# Radio.net
KiCad netlist of a schematic drawn in Altium Designer
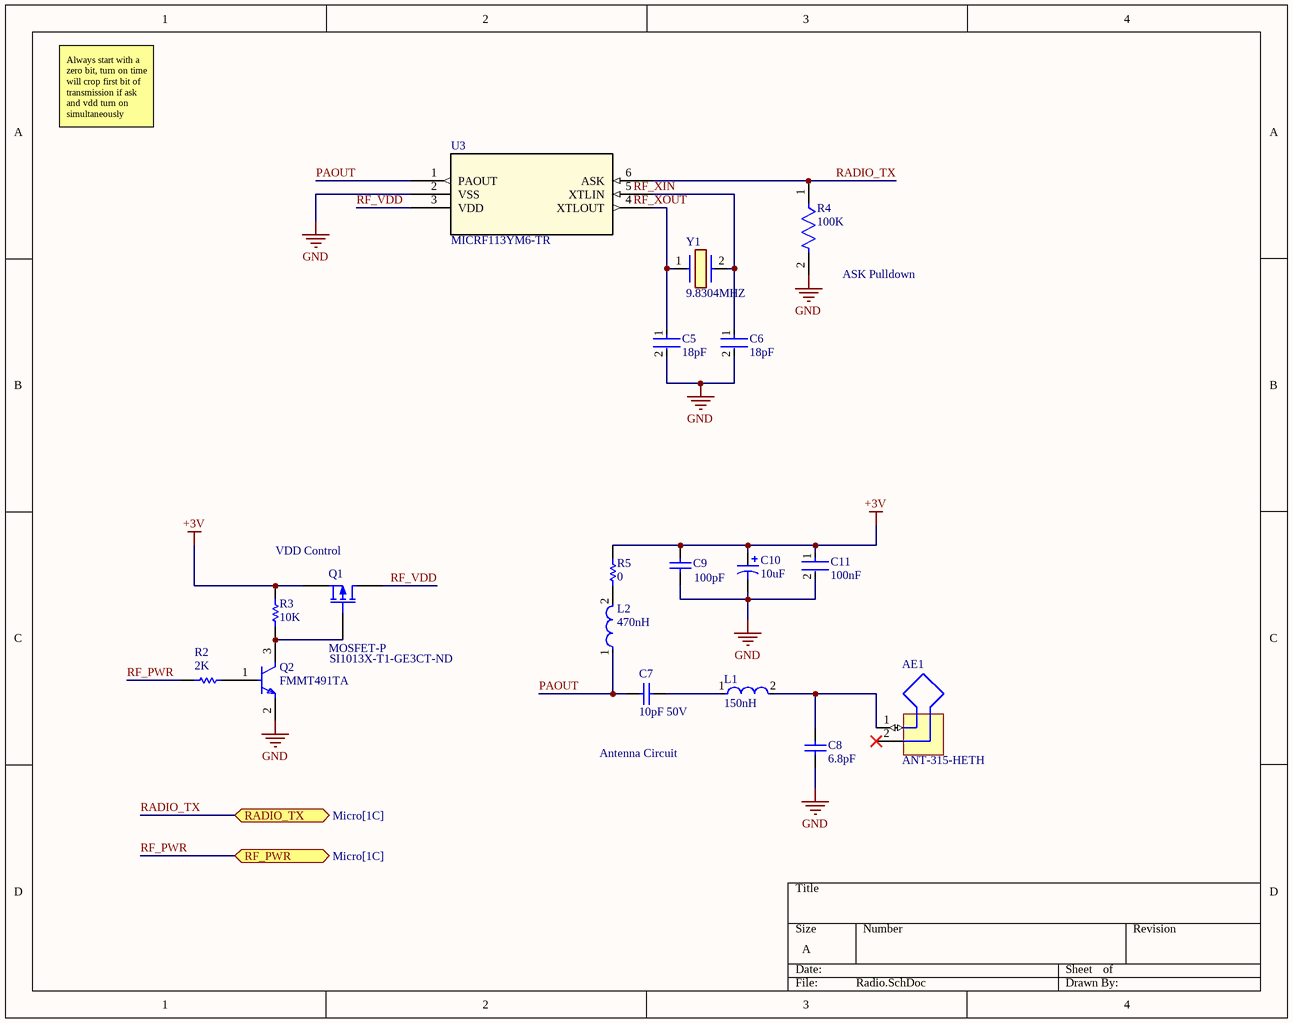
[diagram p0: Radio.SchDoc]

(export (version "E")
  (design (tool "Eeschema 10.0.6"))
  (components
    (comp (ref "AE1")
      (value "ANT-315-HETH")
      (footprint "ANT-xxx-HETH")
      (description "Embeddable 1/4-wave Monopole Antenna, HE Series, 315MHz, Thru-Hole")
      (libsource (lib "Altium Content Vault") (part "ANT-XXX-HEYY"))
    )
    (comp (ref "C5")
      (value "18pF")
      (footprint "FP-0402-L_1_0_1-W_0_5_0_1-MFG")
      (description "General Purpose Ceramic Capacitor, 0402, 18pF, 5%, C0G, 30ppm/°C, 50V")
      (fields (field (name "VOLTAGE") "50V") (field (name "TOLERANCE") "5%"))
      (libsource (lib "Altium Content Vault") (part "b4654b650e69147ec39a6b967a45e02"))
    )
    (comp (ref "C6")
      (value "18pF")
      (footprint "FP-0402-L_1_0_1-W_0_5_0_1-MFG")
      (description "General Purpose Ceramic Capacitor, 0402, 18pF, 5%, C0G, 30ppm/°C, 50V")
      (fields (field (name "VOLTAGE") "50V") (field (name "TOLERANCE") "5%"))
      (libsource (lib "Altium Content Vault") (part "b4654b650e69147ec39a6b967a45e02"))
    )
    (comp (ref "C7")
      (value "10pF 50V")
      (footprint "CAPC1608X90X35LL10T15")
      (fields (field (name "PART NUMBER") "GRM1885C1H100JA01D") (field (name "MANUFACTURER") "Murata"))
      (libsource (lib "Altium Content Vault") (part "CAP"))
    )
    (comp (ref "C8")
      (value "6.8pF")
      (footprint "CAPC1005X55X25NL05T10")
      (fields (field (name "MANUFACTURER") "Murata") (field (name "PART NUMBER") "GRM1555C1H6R8DA01D"))
      (libsource (lib "Altium Content Vault") (part "CAP"))
    )
    (comp (ref "C9")
      (value "100pF")
      (footprint "CAPC1608X90X35NL10T15")
      (fields (field (name "PART NUMBER") "GRM1885C1H101JA01D") (field (name "MANUFACTURER") "Murata"))
      (libsource (lib "Altium Content Vault") (part "CAP"))
    )
    (comp (ref "C10")
      (value "10uF")
      (footprint "C0805")
      (description "Alum. Electrolytic Cap 10µF 50V; 5mm Surface Mount; Lifetime 2000h; +105°C")
      (fields
        (field (name "MANUFACTURER") "Wurth Electronics")
        (field (name "MANUFACTURER PART NUMBER") "865080642006")
        (field (name "PUBLISHER") "Altium Limited")
      )
      (libsource (lib "Miscellaneous Devices") (part "Cap Pol3"))
    )
    (comp (ref "C11")
      (value "100nF")
      (footprint "FP-C0402-BB-MFG")
      (description "CAP CER 0.1UF 10V X5R 0402")
      (fields (field (name "MANUFACTURER") "Kemet") (field (name "TOLERANCE") "0.1"))
      (libsource (lib "Altium Content Vault") (part "b4654b650e69147ec39a6b967a45e02"))
    )
    (comp (ref "L1")
      (value "150nH")
      (footprint "FP-LQM18NN_00-IPC_B")
      (description "Multilayer Type Inductor for General Circuits, 0603 (1608), 150nH, 10%, 0.6Ω, 50mA")
      (fields (field (name "TOLERANCE") "10%"))
      (libsource (lib "Altium Content Vault") (part "725321dda6339637d4d059423bc1c3c"))
    )
    (comp (ref "L2")
      (value "470nH")
      (footprint "FP-LQW2UAS_00-MFG")
      (description "Wire Wound RF Inductor 470nH ±5% 470mA 1.19Ω 1008 (2520)")
      (fields (field (name "TOLERANCE") "5%"))
      (libsource (lib "Altium Content Vault") (part "725321dda6339637d4d059423bc1c3c"))
    )
    (comp (ref "Q1")
      (value "MOSFET-P")
      (footprint "NTE4153NT1G:SC89-3_0P95X1P7_ONS")
      (description "Single P-Channel 20 V 1.2 Ohm Surface Mount Power Mosfet - SC-89")
      (fields
        (field (name "SUPPLIER PART NUMBER 1") "SI1013X-T1-GE3CT-ND")
        (field (name "MANUFACTURER") "Vishay Siliconix")
        (field (name "MANUFACTURER PART NUMBER") "SI1013X-T1-GE3")
        (field (name "PUBLISHER") "Altium Limited")
      )
      (libsource (lib "Miscellaneous Devices") (part "MOSFET-P"))
    )
    (comp (ref "Q2")
      (value "FMMT491TA")
      (footprint "FP-SOT23-MFG")
      (description "TRANS NPN 60V 1A SOT23-3")
      (libsource (lib "Altium Content Vault") (part "b44e953556f554d0102664c7d152cb4"))
    )
    (comp (ref "R2")
      (value "2K")
      (footprint "RESC1005X40X25LL05T05")
      (description "Chip Resistor, 2 KOhm, +/- 1%, 0.1 W, -55 to 155 degC, 0402 (1005 Metric), RoHS, Tape and Reel")
      (fields (field (name "TOLERANCE") "1%") (field (name "MANUFACTURER") "Panasonic"))
      (libsource (lib "Altium Content Vault") (part "RES-2"))
    )
    (comp (ref "R3")
      (value "10K")
      (footprint "RESC1005X40X25LL05T05")
      (description "Chip Resistor, 10 KOhm, +/- 1%, 0.1 W, -55 to 155 degC, 0402 (1005 Metric), RoHS, Tape and Reel")
      (fields (field (name "TOLERANCE") "1%") (field (name "MANUFACTURER") "Panasonic"))
      (libsource (lib "Altium Content Vault") (part "RES-2"))
    )
    (comp (ref "R4")
      (value "100K")
      (footprint "FP-ERJ2RK-IPC_C")
      (description "RES SMD 100K OHM 1% 1/10W 0402")
      (fields (field (name "TOLERANCE") "1%"))
      (libsource (lib "Altium Content Vault") (part "1029c3af85768c4190bb7ad29bc67b5"))
    )
    (comp (ref "R5")
      (value "0")
      (footprint "RESC1005X40X25LL05T05")
      (description "Chip Resistor, 0 Ohm, 0.1 W, -55 to 155 degC, 0402 (1005 Metric), RoHS, Tape and Reel")
      (fields (field (name "MANUFACTURER") "Panasonic") (field (name "TOLERANCE") "5%"))
      (libsource (lib "Altium Content Vault") (part "RES-2"))
    )
    (comp (ref "U3")
      (value "MICRF113YM6-TR")
      (footprint "SOT23-6_N")
      (description "No Description Available")
      (fields (field (name "COPYRIGHT") "Copyright (C) 2022 Ultra Librarian. All rights reserved."))
      (libsource (lib "MICRF113YM6-TR") (part "MICRF113YM6-TR"))
    )
    (comp (ref "Y1")
      (value "9.8304MHZ")
      (footprint "SamacSys:HC/49US-(AT49)_1")
      (description "Crystal or Oscillator")
      (fields
        (field (name "MANUFACTURER_PART_NUMBER") "ABLS2-16.000MHZ-D4Y-T")
        (field (name "MOUSER PART NUMBER") "815-ABLS2-16-D4Y-T")
      )
      (libsource (lib "*") (part "ABLS2-16.000MHZ-D4Y-T"))
    )
  )
  (nets
    (net (code "1") (name "+3V") (class "Default")
      (node (ref "C10") (pin "1") (pinfunction "1_1") (pintype "passive"))
      (node (ref "C11") (pin "1") (pinfunction "1_1") (pintype "passive"))
      (node (ref "C9") (pin "2") (pinfunction "2_2") (pintype "passive"))
      (node (ref "Q1") (pin "3") (pinfunction "S_3") (pintype "passive"))
      (node (ref "R3") (pin "2") (pinfunction "2_2") (pintype "passive"))
      (node (ref "R5") (pin "2") (pinfunction "2_2") (pintype "passive"))
    )
    (net (code "2") (name "/PAOUT") (class "Default")
      (node (ref "C7") (pin "1") (pinfunction "1_1") (pintype "passive"))
      (node (ref "L2") (pin "1") (pinfunction "1_1") (pintype "passive"))
      (node (ref "U3") (pin "1") (pinfunction "PAOUT_1") (pintype "output"))
    )
    (net (code "3") (name "/RADIO_TX") (class "Default")
      (node (ref "R4") (pin "1") (pinfunction "1_1") (pintype "passive"))
      (node (ref "U3") (pin "6") (pinfunction "ASK_6") (pintype "input"))
    )
    (net (code "4") (name "/RF_PWR") (class "Default")
      (node (ref "R2") (pin "1") (pinfunction "1_1") (pintype "passive"))
    )
    (net (code "5") (name "/RF_VDD") (class "Default")
      (node (ref "Q1") (pin "1") (pinfunction "D_1") (pintype "passive"))
      (node (ref "U3") (pin "3") (pinfunction "VDD_3") (pintype "power_in"))
    )
    (net (code "8") (name "GND") (class "Default")
      (node (ref "C10") (pin "2") (pinfunction "2_2") (pintype "passive"))
      (node (ref "C11") (pin "2") (pinfunction "2_2") (pintype "passive"))
      (node (ref "C5") (pin "2") (pinfunction "2_2") (pintype "passive"))
      (node (ref "C6") (pin "2") (pinfunction "2_2") (pintype "passive"))
      (node (ref "C8") (pin "1") (pinfunction "1_1") (pintype "passive"))
      (node (ref "C9") (pin "1") (pinfunction "1_1") (pintype "passive"))
      (node (ref "Q2") (pin "2") (pinfunction "E_2") (pintype "passive"))
      (node (ref "R4") (pin "2") (pinfunction "2_2") (pintype "passive"))
      (node (ref "U3") (pin "2") (pinfunction "VSS_2") (pintype "power_in"))
    )
    (net (code "9") (name "Net-(AE1-High_Band_Feed)") (class "Default")
      (node (ref "AE1") (pin "1") (pinfunction "High_Band_Feed_1") (pintype "bidirectional"))
      (node (ref "C8") (pin "2") (pinfunction "2_2") (pintype "passive"))
      (node (ref "L1") (pin "2") (pinfunction "2_2") (pintype "passive"))
    )
    (net (code "10") (name "Net-(C7-Pad2)") (class "Default")
      (node (ref "C7") (pin "2") (pinfunction "2_2") (pintype "passive"))
      (node (ref "L1") (pin "1") (pinfunction "1_1") (pintype "passive"))
    )
    (net (code "11") (name "Net-(L2-Pad2)") (class "Default")
      (node (ref "L2") (pin "2") (pinfunction "2_2") (pintype "passive"))
      (node (ref "R5") (pin "1") (pinfunction "1_1") (pintype "passive"))
    )
    (net (code "12") (name "Net-(Q1-G)") (class "Default")
      (node (ref "Q1") (pin "2") (pinfunction "G_2") (pintype "passive"))
      (node (ref "Q2") (pin "3") (pinfunction "C_3") (pintype "passive"))
      (node (ref "R3") (pin "1") (pinfunction "1_1") (pintype "passive"))
    )
    (net (code "13") (name "Net-(Q2-B)") (class "Default")
      (node (ref "Q2") (pin "1") (pinfunction "B_1") (pintype "passive"))
      (node (ref "R2") (pin "2") (pinfunction "2_2") (pintype "passive"))
    )
    (net (code "14") (name "Net-(U3-XTLIN)") (class "Default")
      (node (ref "C6") (pin "1") (pinfunction "1_1") (pintype "passive"))
      (node (ref "U3") (pin "5") (pinfunction "XTLIN_5") (pintype "input"))
      (node (ref "Y1") (pin "2") (pinfunction "2_2") (pintype "passive"))
    )
    (net (code "15") (name "Net-(U3-XTLOUT)") (class "Default")
      (node (ref "C5") (pin "1") (pinfunction "1_1") (pintype "passive"))
      (node (ref "U3") (pin "4") (pinfunction "XTLOUT_4") (pintype "output"))
      (node (ref "Y1") (pin "1") (pinfunction "1_1") (pintype "passive"))
    )
    (net (code "16") (name "unconnected-(AE1-Low_Band_Feed-Pad2)") (class "Default")
      (node (ref "AE1") (pin "2") (pinfunction "Low_Band_Feed_2") (pintype "passive+no_connect"))
    )
  )
)
